# UKU208_eth.net
KiCad netlist of a schematic drawn in Altium Designer
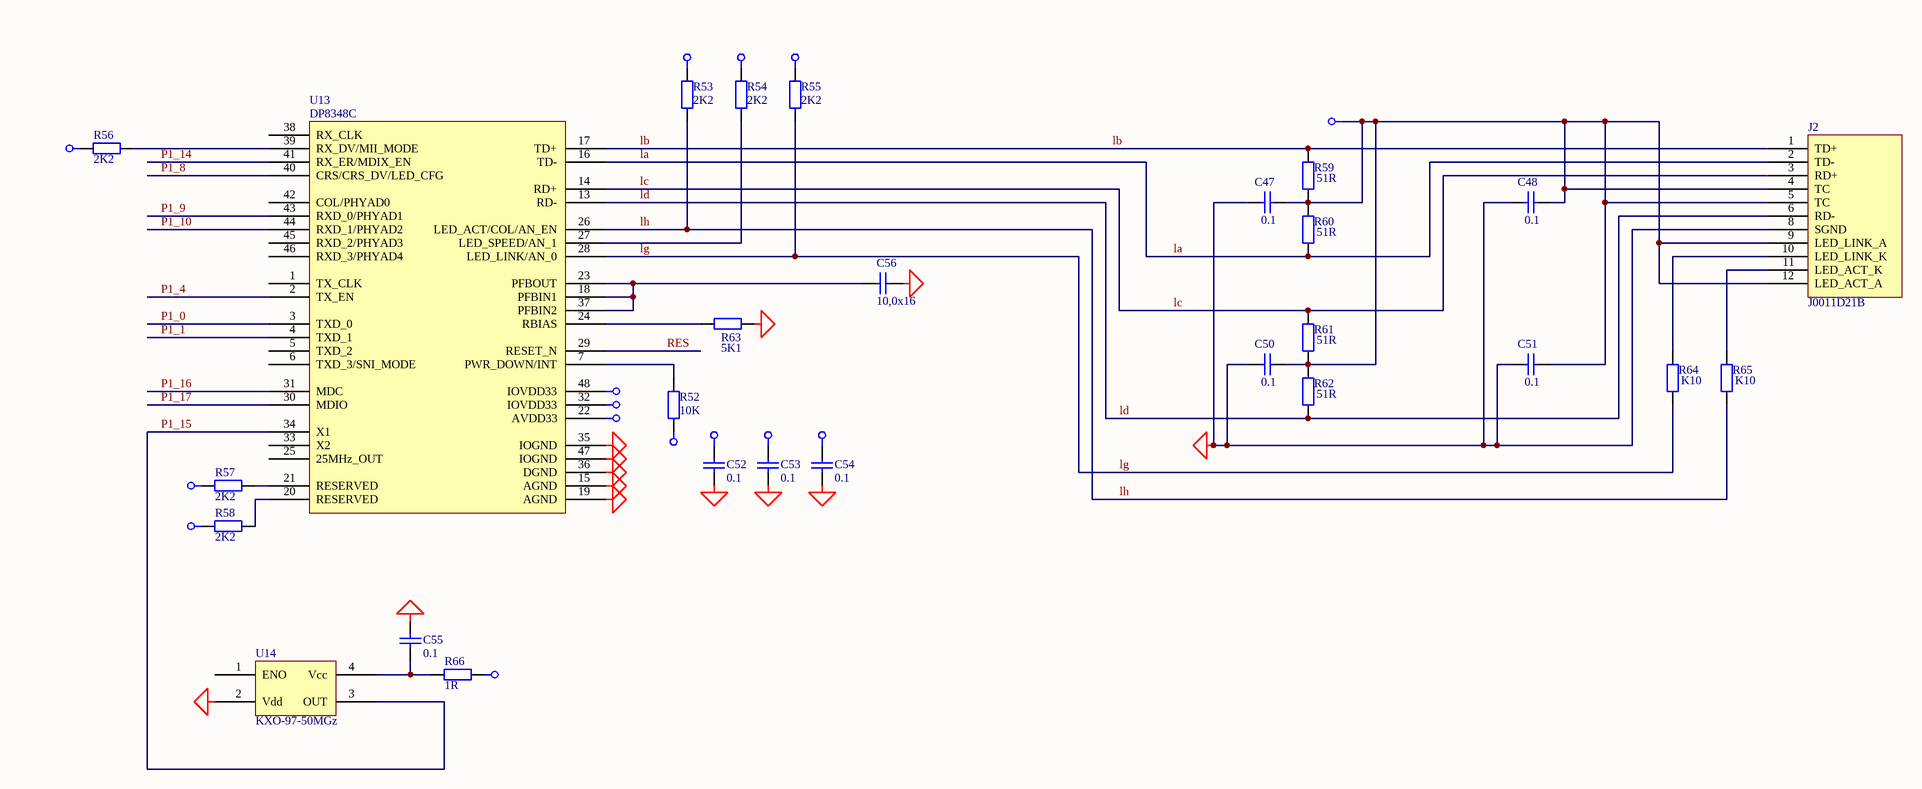
[diagram p0: UKU208_eth.SchDoc]

(export (version "E")
  (design (tool "Eeschema 10.0.6"))
  (components
    (comp (ref "C47")
      (value "0.1")
      (footprint "_1206")
      (description "Capacitor (Semiconductor SIM Model)")
      (fields (field (name "MANUFACTURER") "Generic Components") (field (name "PUBLISHER") "Altium Limited"))
      (libsource (lib "Miscellaneous Devices") (part "Cap Semi"))
    )
    (comp (ref "C48")
      (value "0.1")
      (footprint "_1206")
      (description "Capacitor (Semiconductor SIM Model)")
      (fields (field (name "MANUFACTURER") "Generic Components") (field (name "PUBLISHER") "Altium Limited"))
      (libsource (lib "Miscellaneous Devices") (part "Cap Semi"))
    )
    (comp (ref "C50")
      (value "0.1")
      (footprint "_1206")
      (description "Capacitor (Semiconductor SIM Model)")
      (fields (field (name "MANUFACTURER") "Generic Components") (field (name "PUBLISHER") "Altium Limited"))
      (libsource (lib "Miscellaneous Devices") (part "Cap Semi"))
    )
    (comp (ref "C51")
      (value "0.1")
      (footprint "_1206")
      (description "Capacitor (Semiconductor SIM Model)")
      (fields (field (name "MANUFACTURER") "Generic Components") (field (name "PUBLISHER") "Altium Limited"))
      (libsource (lib "Miscellaneous Devices") (part "Cap Semi"))
    )
    (comp (ref "C52")
      (value "0.1")
      (footprint "_1206")
      (description "Capacitor (Semiconductor SIM Model)")
      (fields (field (name "MANUFACTURER") "Generic Components") (field (name "PUBLISHER") "Altium Limited"))
      (libsource (lib "Miscellaneous Devices") (part "Cap Semi"))
    )
    (comp (ref "C53")
      (value "0.1")
      (footprint "_1206")
      (description "Capacitor (Semiconductor SIM Model)")
      (fields (field (name "MANUFACTURER") "Generic Components") (field (name "PUBLISHER") "Altium Limited"))
      (libsource (lib "Miscellaneous Devices") (part "Cap Semi"))
    )
    (comp (ref "C54")
      (value "0.1")
      (footprint "_1206")
      (description "Capacitor (Semiconductor SIM Model)")
      (fields (field (name "MANUFACTURER") "Generic Components") (field (name "PUBLISHER") "Altium Limited"))
      (libsource (lib "Miscellaneous Devices") (part "Cap Semi"))
    )
    (comp (ref "C55")
      (value "0.1")
      (footprint "_1206")
      (description "Capacitor (Semiconductor SIM Model)")
      (fields (field (name "MANUFACTURER") "Generic Components") (field (name "PUBLISHER") "Altium Limited"))
      (libsource (lib "Miscellaneous Devices") (part "Cap Semi"))
    )
    (comp (ref "C56")
      (value "10,0x16")
      (footprint "_1206")
      (description "Capacitor (Semiconductor SIM Model)")
      (fields (field (name "MANUFACTURER") "Generic Components") (field (name "PUBLISHER") "Altium Limited"))
      (libsource (lib "Miscellaneous Devices") (part "Cap Semi"))
    )
    (comp (ref "J2") (value "J0011D21B") (footprint "J0011D21B") (libsource (lib "PAL") (part "J0011D21B")))
    (comp (ref "R52")
      (value "10K")
      (footprint "_1206")
      (description "Resistor")
      (fields (field (name "MANUFACTURER") "Generic Components") (field (name "PUBLISHER") "Altium Limited"))
      (libsource (lib "Miscellaneous Devices") (part "Res2"))
    )
    (comp (ref "R53")
      (value "2K2")
      (footprint "_1206")
      (description "Resistor")
      (fields (field (name "MANUFACTURER") "Generic Components") (field (name "PUBLISHER") "Altium Limited"))
      (libsource (lib "") (part "Res2_2"))
    )
    (comp (ref "R54")
      (value "2K2")
      (footprint "_1206")
      (description "Resistor")
      (fields (field (name "MANUFACTURER") "Generic Components") (field (name "PUBLISHER") "Altium Limited"))
      (libsource (lib "") (part "Res2_2"))
    )
    (comp (ref "R55")
      (value "2K2")
      (footprint "_1206")
      (description "Resistor")
      (fields (field (name "MANUFACTURER") "Generic Components") (field (name "PUBLISHER") "Altium Limited"))
      (libsource (lib "") (part "Res2_2"))
    )
    (comp (ref "R56")
      (value "2K2")
      (footprint "_1206")
      (description "Resistor")
      (fields (field (name "MANUFACTURER") "Generic Components") (field (name "PUBLISHER") "Altium Limited"))
      (libsource (lib "") (part "Res2_1"))
    )
    (comp (ref "R57")
      (value "2K2")
      (footprint "_1206")
      (description "Resistor")
      (fields (field (name "MANUFACTURER") "Generic Components") (field (name "PUBLISHER") "Altium Limited"))
      (libsource (lib "") (part "Res2_1"))
    )
    (comp (ref "R58")
      (value "2K2")
      (footprint "_1206")
      (description "Resistor")
      (fields (field (name "MANUFACTURER") "Generic Components") (field (name "PUBLISHER") "Altium Limited"))
      (libsource (lib "") (part "Res2_1"))
    )
    (comp (ref "R59")
      (value "51R")
      (footprint "_1206")
      (description "Resistor")
      (fields (field (name "MANUFACTURER") "Generic Components") (field (name "PUBLISHER") "Altium Limited"))
      (libsource (lib "Miscellaneous Devices") (part "Res2"))
    )
    (comp (ref "R60")
      (value "51R")
      (footprint "_1206")
      (description "Resistor")
      (fields (field (name "MANUFACTURER") "Generic Components") (field (name "PUBLISHER") "Altium Limited"))
      (libsource (lib "Miscellaneous Devices") (part "Res2"))
    )
    (comp (ref "R61")
      (value "51R")
      (footprint "_1206")
      (description "Resistor")
      (fields (field (name "MANUFACTURER") "Generic Components") (field (name "PUBLISHER") "Altium Limited"))
      (libsource (lib "Miscellaneous Devices") (part "Res2"))
    )
    (comp (ref "R62")
      (value "51R")
      (footprint "_1206")
      (description "Resistor")
      (fields (field (name "MANUFACTURER") "Generic Components") (field (name "PUBLISHER") "Altium Limited"))
      (libsource (lib "Miscellaneous Devices") (part "Res2"))
    )
    (comp (ref "R63")
      (value "5K1")
      (footprint "_1206")
      (description "Resistor")
      (fields (field (name "MANUFACTURER") "Generic Components") (field (name "PUBLISHER") "Altium Limited"))
      (libsource (lib "") (part "Res2_1"))
    )
    (comp (ref "R64")
      (value "K10")
      (footprint "_1206")
      (description "Resistor")
      (fields (field (name "MANUFACTURER") "Generic Components") (field (name "PUBLISHER") "Altium Limited"))
      (libsource (lib "Miscellaneous Devices") (part "Res2"))
    )
    (comp (ref "R65")
      (value "K10")
      (footprint "_1206")
      (description "Resistor")
      (fields (field (name "MANUFACTURER") "Generic Components") (field (name "PUBLISHER") "Altium Limited"))
      (libsource (lib "Miscellaneous Devices") (part "Res2"))
    )
    (comp (ref "R66")
      (value "1R")
      (footprint "_1206")
      (description "Resistor")
      (fields (field (name "MANUFACTURER") "Generic Components") (field (name "PUBLISHER") "Altium Limited"))
      (libsource (lib "") (part "Res2_3"))
    )
    (comp (ref "U13") (value "DP8348C") (footprint "F-QFP7X7-G48/N") (libsource (lib "PAL") (part "DP8348C")))
    (comp (ref "U14") (value "KXO-97-50MGz") (footprint "KXO-97") (libsource (lib "PAL") (part "KXO-97")))
  )
  (nets
    (net (code "1") (name "+3v3") (class "Default")
      (node (ref "C47") (pin "2") (pinfunction "2_2") (pintype "passive"))
      (node (ref "C48") (pin "2") (pinfunction "2_2") (pintype "passive"))
      (node (ref "C50") (pin "2") (pinfunction "2_2") (pintype "passive"))
      (node (ref "C51") (pin "2") (pinfunction "2_2") (pintype "passive"))
      (node (ref "C52") (pin "1") (pinfunction "1_1") (pintype "passive"))
      (node (ref "C53") (pin "1") (pinfunction "1_1") (pintype "passive"))
      (node (ref "C54") (pin "1") (pinfunction "1_1") (pintype "passive"))
      (node (ref "J2") (pin "12") (pinfunction "LED_ACT_A_12") (pintype "passive"))
      (node (ref "J2") (pin "4") (pinfunction "TC_4") (pintype "passive"))
      (node (ref "J2") (pin "5") (pinfunction "TC_5") (pintype "passive"))
      (node (ref "J2") (pin "9") (pinfunction "LED_LINK_A_9") (pintype "passive"))
      (node (ref "R52") (pin "2") (pinfunction "2_2") (pintype "passive"))
      (node (ref "R53") (pin "2") (pinfunction "2_2") (pintype "passive"))
      (node (ref "R54") (pin "2") (pinfunction "2_2") (pintype "passive"))
      (node (ref "R55") (pin "2") (pinfunction "2_2") (pintype "passive"))
      (node (ref "R56") (pin "2") (pinfunction "2_2") (pintype "passive"))
      (node (ref "R57") (pin "2") (pinfunction "2_2") (pintype "passive"))
      (node (ref "R58") (pin "2") (pinfunction "2_2") (pintype "passive"))
      (node (ref "R59") (pin "2") (pinfunction "2_2") (pintype "passive"))
      (node (ref "R60") (pin "1") (pinfunction "1_1") (pintype "passive"))
      (node (ref "R61") (pin "2") (pinfunction "2_2") (pintype "passive"))
      (node (ref "R62") (pin "1") (pinfunction "1_1") (pintype "passive"))
      (node (ref "U13") (pin "22") (pinfunction "AVDD33_22") (pintype "passive"))
      (node (ref "U13") (pin "32") (pinfunction "IOVDD33_32") (pintype "passive"))
      (node (ref "U13") (pin "48") (pinfunction "IOVDD33_48") (pintype "passive"))
    )
    (net (code "2") (name "+5v") (class "Default")
      (node (ref "R66") (pin "2") (pinfunction "2_2") (pintype "passive"))
    )
    (net (code "3") (name "/P1_0") (class "Default")
      (node (ref "U13") (pin "3") (pinfunction "TXD_0_3") (pintype "passive"))
    )
    (net (code "4") (name "/P1_1") (class "Default")
      (node (ref "U13") (pin "4") (pinfunction "TXD_1_4") (pintype "passive"))
    )
    (net (code "5") (name "/P1_4") (class "Default")
      (node (ref "U13") (pin "2") (pinfunction "TX_EN_2") (pintype "passive"))
    )
    (net (code "6") (name "/P1_8") (class "Default")
      (node (ref "U13") (pin "40") (pinfunction "CRS/CRS_DV/LED_CFG_40") (pintype "passive"))
    )
    (net (code "7") (name "/P1_9") (class "Default")
      (node (ref "U13") (pin "43") (pinfunction "RXD_0/PHYAD1_43") (pintype "passive"))
    )
    (net (code "8") (name "/P1_10") (class "Default")
      (node (ref "U13") (pin "44") (pinfunction "RXD_1/PHYAD2_44") (pintype "passive"))
    )
    (net (code "9") (name "/P1_14") (class "Default")
      (node (ref "U13") (pin "41") (pinfunction "RX_ER/MDIX_EN_41") (pintype "passive"))
    )
    (net (code "10") (name "/P1_15") (class "Default")
      (node (ref "U13") (pin "34") (pinfunction "X1_34") (pintype "passive"))
      (node (ref "U14") (pin "3") (pinfunction "OUT_3") (pintype "passive"))
    )
    (net (code "11") (name "/P1_16") (class "Default")
      (node (ref "U13") (pin "31") (pinfunction "MDC_31") (pintype "passive"))
    )
    (net (code "12") (name "/P1_17") (class "Default")
      (node (ref "U13") (pin "30") (pinfunction "MDIO_30") (pintype "passive"))
    )
    (net (code "13") (name "/RES") (class "Default")
      (node (ref "U13") (pin "29") (pinfunction "RESET_N_29") (pintype "passive"))
    )
    (net (code "14") (name "/la") (class "Default")
      (node (ref "J2") (pin "2") (pinfunction "TD-_2") (pintype "passive"))
      (node (ref "R60") (pin "2") (pinfunction "2_2") (pintype "passive"))
      (node (ref "U13") (pin "16") (pinfunction "TD-_16") (pintype "passive"))
    )
    (net (code "15") (name "/lb") (class "Default")
      (node (ref "J2") (pin "1") (pinfunction "TD+_1") (pintype "passive"))
      (node (ref "R59") (pin "1") (pinfunction "1_1") (pintype "passive"))
      (node (ref "U13") (pin "17") (pinfunction "TD+_17") (pintype "passive"))
    )
    (net (code "16") (name "/lc") (class "Default")
      (node (ref "J2") (pin "3") (pinfunction "RD+_3") (pintype "passive"))
      (node (ref "R61") (pin "1") (pinfunction "1_1") (pintype "passive"))
      (node (ref "U13") (pin "14") (pinfunction "RD+_14") (pintype "passive"))
    )
    (net (code "17") (name "/ld") (class "Default")
      (node (ref "J2") (pin "6") (pinfunction "RD-_6") (pintype "passive"))
      (node (ref "R62") (pin "2") (pinfunction "2_2") (pintype "passive"))
      (node (ref "U13") (pin "13") (pinfunction "RD-_13") (pintype "passive"))
    )
    (net (code "18") (name "/lg") (class "Default")
      (node (ref "R55") (pin "1") (pinfunction "1_1") (pintype "passive"))
      (node (ref "R64") (pin "2") (pinfunction "2_2") (pintype "passive"))
      (node (ref "U13") (pin "28") (pinfunction "LED_LINK/AN_0_28") (pintype "passive"))
    )
    (net (code "19") (name "/lh") (class "Default")
      (node (ref "R53") (pin "1") (pinfunction "1_1") (pintype "passive"))
      (node (ref "R65") (pin "2") (pinfunction "2_2") (pintype "passive"))
      (node (ref "U13") (pin "26") (pinfunction "LED_ACT/COL/AN_EN_26") (pintype "passive"))
    )
    (net (code "20") (name "GND") (class "Default")
      (node (ref "C47") (pin "1") (pinfunction "1_1") (pintype "passive"))
      (node (ref "C48") (pin "1") (pinfunction "1_1") (pintype "passive"))
      (node (ref "C50") (pin "1") (pinfunction "1_1") (pintype "passive"))
      (node (ref "C51") (pin "1") (pinfunction "1_1") (pintype "passive"))
      (node (ref "C52") (pin "2") (pinfunction "2_2") (pintype "passive"))
      (node (ref "C53") (pin "2") (pinfunction "2_2") (pintype "passive"))
      (node (ref "C54") (pin "2") (pinfunction "2_2") (pintype "passive"))
      (node (ref "C55") (pin "2") (pinfunction "2_2") (pintype "passive"))
      (node (ref "C56") (pin "2") (pinfunction "2_2") (pintype "passive"))
      (node (ref "J2") (pin "8") (pinfunction "SGND_8") (pintype "passive"))
      (node (ref "R63") (pin "1") (pinfunction "1_1") (pintype "passive"))
      (node (ref "U13") (pin "15") (pinfunction "AGND_15") (pintype "passive"))
      (node (ref "U13") (pin "19") (pinfunction "AGND_19") (pintype "passive"))
      (node (ref "U13") (pin "35") (pinfunction "IOGND_35") (pintype "passive"))
      (node (ref "U13") (pin "36") (pinfunction "DGND_36") (pintype "passive"))
      (node (ref "U13") (pin "47") (pinfunction "IOGND_47") (pintype "passive"))
      (node (ref "U14") (pin "2") (pinfunction "Vdd_2") (pintype "passive"))
    )
    (net (code "21") (name "Net-(J2-LED_ACT_K)") (class "Default")
      (node (ref "J2") (pin "11") (pinfunction "LED_ACT_K_11") (pintype "passive"))
      (node (ref "R65") (pin "1") (pinfunction "1_1") (pintype "passive"))
    )
    (net (code "22") (name "Net-(J2-LED_LINK_K)") (class "Default")
      (node (ref "J2") (pin "10") (pinfunction "LED_LINK_K_10") (pintype "passive"))
      (node (ref "R64") (pin "1") (pinfunction "1_1") (pintype "passive"))
    )
    (net (code "23") (name "Net-(R57-Pad1)") (class "Default")
      (node (ref "R57") (pin "1") (pinfunction "1_1") (pintype "passive"))
      (node (ref "U13") (pin "21") (pinfunction "RESERVED_21") (pintype "passive"))
    )
    (net (code "24") (name "Net-(R58-Pad1)") (class "Default")
      (node (ref "R58") (pin "1") (pinfunction "1_1") (pintype "passive"))
      (node (ref "U13") (pin "20") (pinfunction "RESERVED_20") (pintype "passive"))
    )
    (net (code "25") (name "Net-(U13-LED_SPEED{slash}AN_1)") (class "Default")
      (node (ref "R54") (pin "1") (pinfunction "1_1") (pintype "passive"))
      (node (ref "U13") (pin "27") (pinfunction "LED_SPEED/AN_1_27") (pintype "passive"))
    )
    (net (code "26") (name "Net-(U13-PFBIN1)") (class "Default")
      (node (ref "C56") (pin "1") (pinfunction "1_1") (pintype "passive"))
      (node (ref "U13") (pin "18") (pinfunction "PFBIN1_18") (pintype "passive"))
      (node (ref "U13") (pin "23") (pinfunction "PFBOUT_23") (pintype "passive"))
      (node (ref "U13") (pin "37") (pinfunction "PFBIN2_37") (pintype "passive"))
    )
    (net (code "27") (name "Net-(U13-PWR_DOWN{slash}INT)") (class "Default")
      (node (ref "R52") (pin "1") (pinfunction "1_1") (pintype "passive"))
      (node (ref "U13") (pin "7") (pinfunction "PWR_DOWN/INT_7") (pintype "passive"))
    )
    (net (code "28") (name "Net-(U13-RBIAS)") (class "Default")
      (node (ref "R63") (pin "2") (pinfunction "2_2") (pintype "passive"))
      (node (ref "U13") (pin "24") (pinfunction "RBIAS_24") (pintype "passive"))
    )
    (net (code "29") (name "Net-(U13-RX_DV{slash}MII_MODE)") (class "Default")
      (node (ref "R56") (pin "1") (pinfunction "1_1") (pintype "passive"))
      (node (ref "U13") (pin "39") (pinfunction "RX_DV/MII_MODE_39") (pintype "passive"))
    )
    (net (code "30") (name "Net-(U14-Vcc)") (class "Default")
      (node (ref "C55") (pin "1") (pinfunction "1_1") (pintype "passive"))
      (node (ref "R66") (pin "1") (pinfunction "1_1") (pintype "passive"))
      (node (ref "U14") (pin "4") (pinfunction "Vcc_4") (pintype "passive"))
    )
    (net (code "31") (name "unconnected-(U13-25MHz_OUT-Pad25)") (class "Default")
      (node (ref "U13") (pin "25") (pinfunction "25MHz_OUT_25") (pintype "passive"))
    )
    (net (code "32") (name "unconnected-(U13-COL{slash}PHYAD0-Pad42)") (class "Default")
      (node (ref "U13") (pin "42") (pinfunction "COL/PHYAD0_42") (pintype "passive"))
    )
    (net (code "33") (name "unconnected-(U13-RXD_2{slash}PHYAD3-Pad45)") (class "Default")
      (node (ref "U13") (pin "45") (pinfunction "RXD_2/PHYAD3_45") (pintype "passive"))
    )
    (net (code "34") (name "unconnected-(U13-RXD_3{slash}PHYAD4-Pad46)") (class "Default")
      (node (ref "U13") (pin "46") (pinfunction "RXD_3/PHYAD4_46") (pintype "passive"))
    )
    (net (code "35") (name "unconnected-(U13-RX_CLK-Pad38)") (class "Default")
      (node (ref "U13") (pin "38") (pinfunction "RX_CLK_38") (pintype "passive"))
    )
    (net (code "36") (name "unconnected-(U13-TXD_2-Pad5)") (class "Default")
      (node (ref "U13") (pin "5") (pinfunction "TXD_2_5") (pintype "passive"))
    )
    (net (code "37") (name "unconnected-(U13-TXD_3{slash}SNI_MODE-Pad6)") (class "Default")
      (node (ref "U13") (pin "6") (pinfunction "TXD_3/SNI_MODE_6") (pintype "passive"))
    )
    (net (code "38") (name "unconnected-(U13-TX_CLK-Pad1)") (class "Default")
      (node (ref "U13") (pin "1") (pinfunction "TX_CLK_1") (pintype "passive"))
    )
    (net (code "39") (name "unconnected-(U13-X2-Pad33)") (class "Default")
      (node (ref "U13") (pin "33") (pinfunction "X2_33") (pintype "passive"))
    )
    (net (code "40") (name "unconnected-(U14-ENO-Pad1)") (class "Default")
      (node (ref "U14") (pin "1") (pinfunction "ENO_1") (pintype "passive"))
    )
  )
)
